# Power.net
KiCad netlist of a schematic drawn in Altium Designer
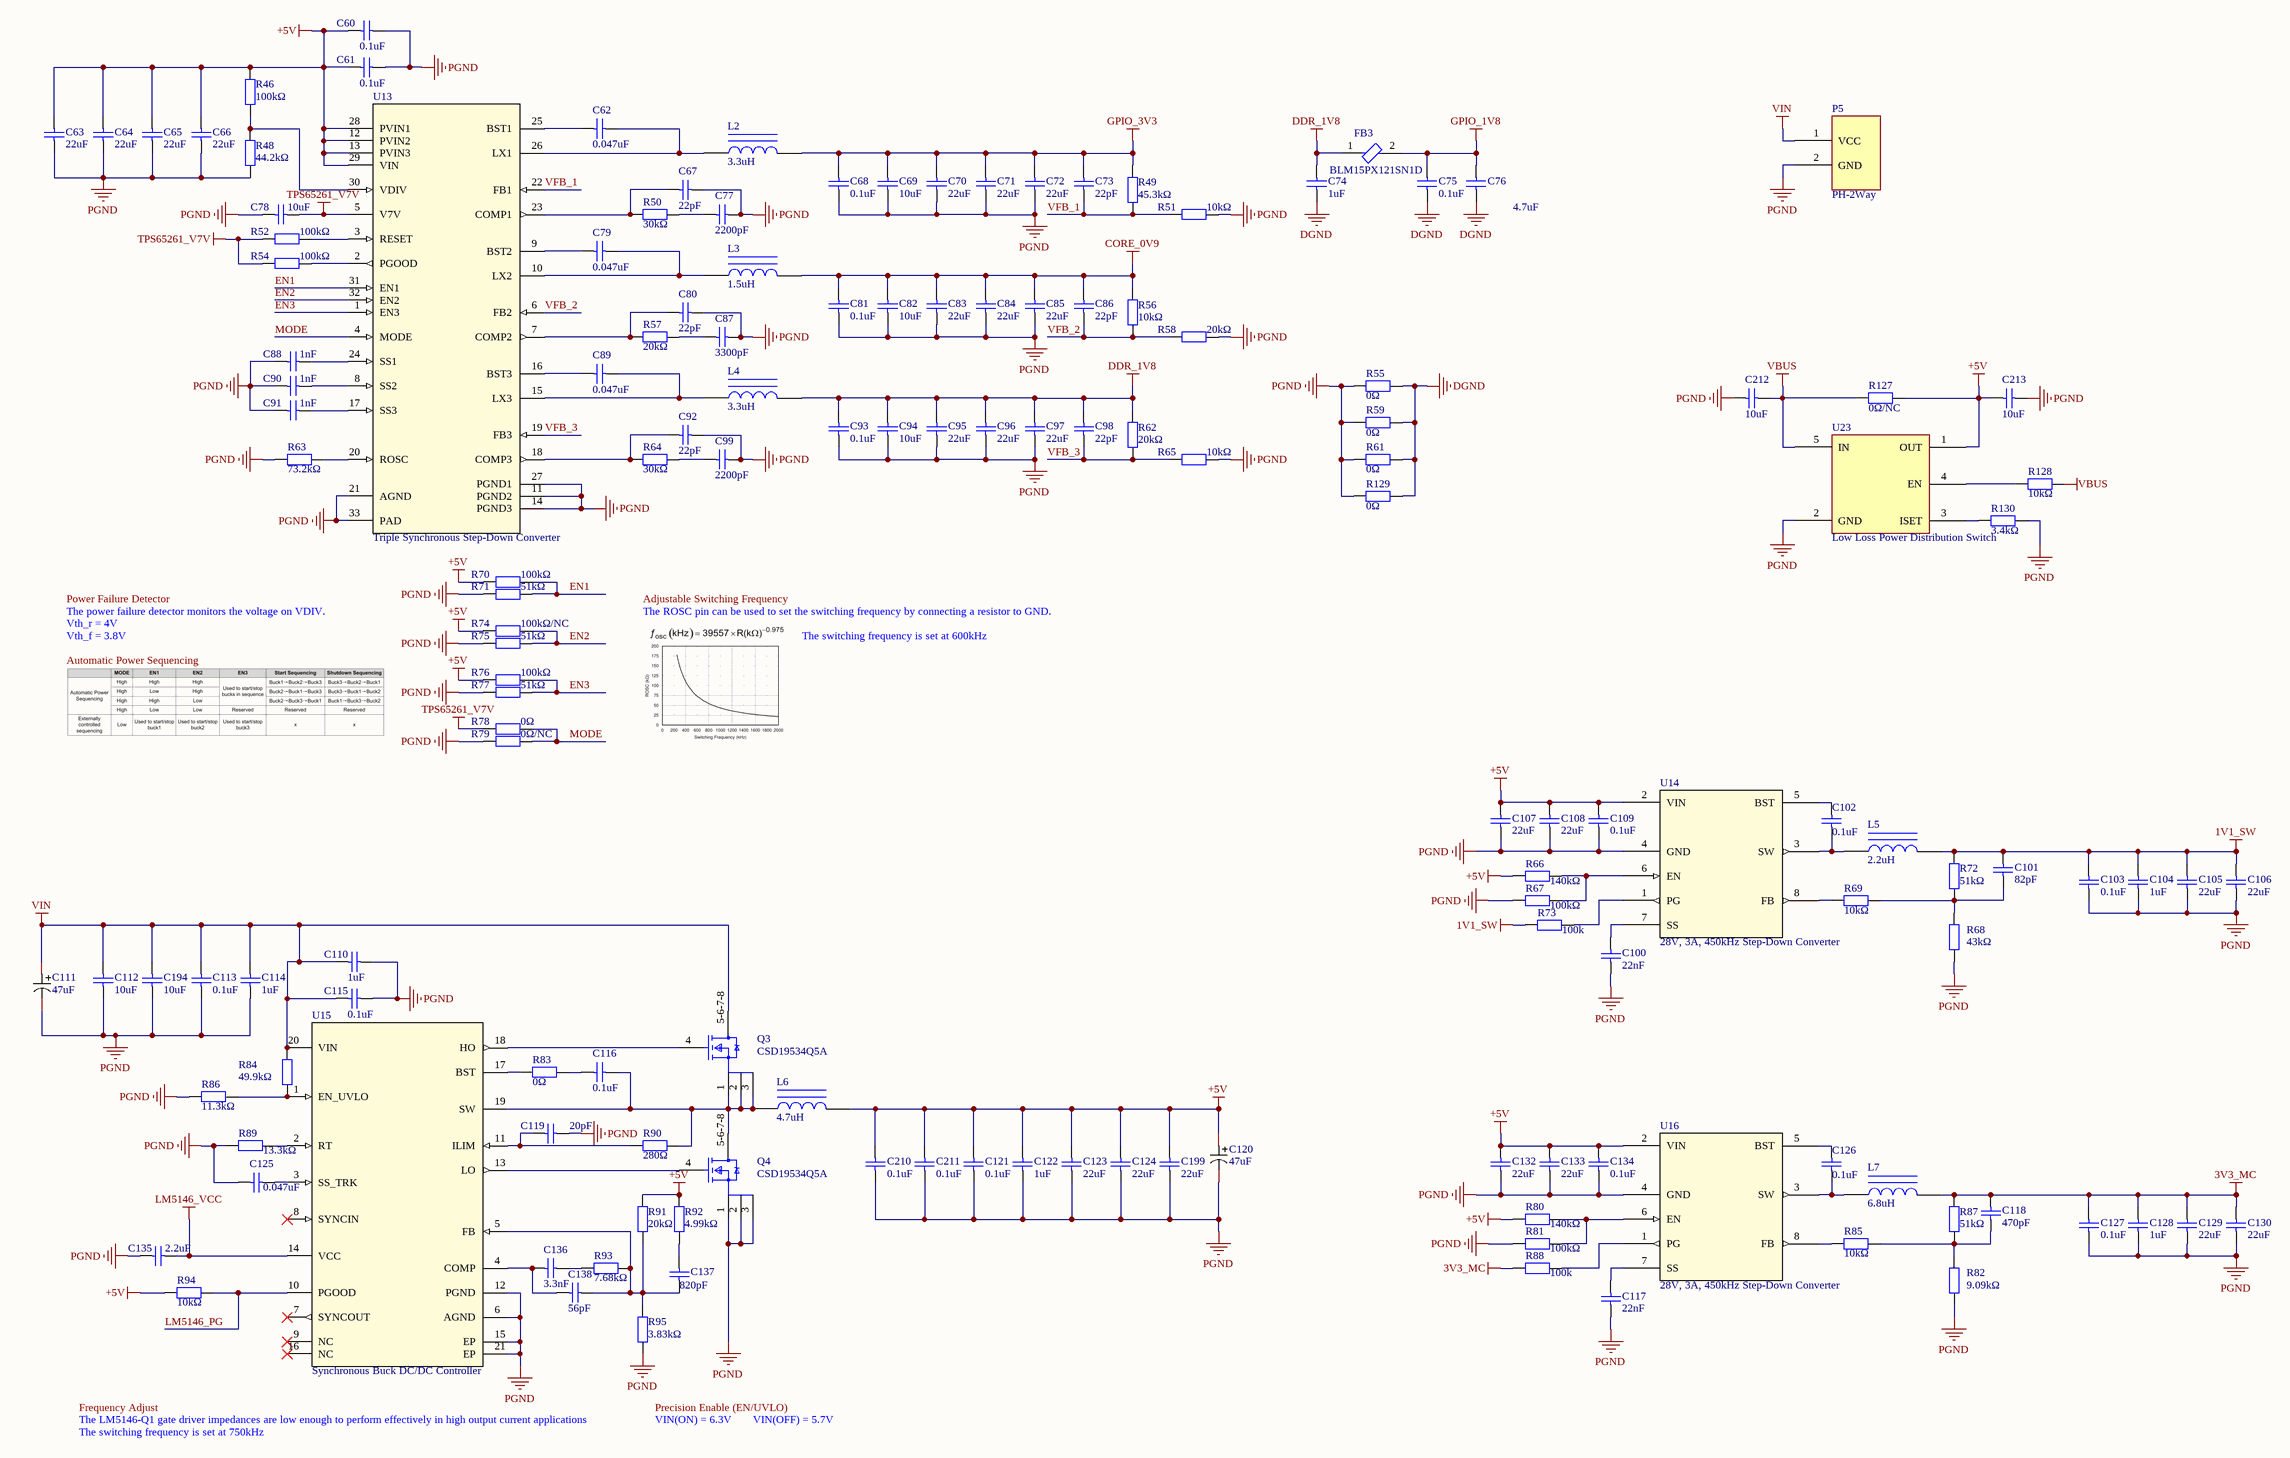
[diagram p0: Power.SchDoc]

(export (version "E")
  (design (tool "Eeschema 10.0.6"))
  (components
    (comp (ref "C60")
      (value "0.1uF")
      (footprint "0603_C")
      (description "贴片电容")
      (libsource (lib "SFerret") (part "SMT_Cap"))
    )
    (comp (ref "C61")
      (value "0.1uF")
      (footprint "0603_C")
      (description "贴片电容")
      (libsource (lib "SFerret") (part "SMT_Cap"))
    )
    (comp (ref "C62")
      (value "0.047uF")
      (footprint "0402_C")
      (description "贴片电容")
      (libsource (lib "SFerret") (part "SMT_Cap"))
    )
    (comp (ref "C63")
      (value "22uF")
      (footprint "1206_C")
      (description "贴片电容")
      (libsource (lib "SFerret") (part "SMT_Cap"))
    )
    (comp (ref "C64")
      (value "22uF")
      (footprint "1206_C")
      (description "贴片电容")
      (libsource (lib "SFerret") (part "SMT_Cap"))
    )
    (comp (ref "C65")
      (value "22uF")
      (footprint "1206_C")
      (description "贴片电容")
      (libsource (lib "SFerret") (part "SMT_Cap"))
    )
    (comp (ref "C66")
      (value "22uF")
      (footprint "1206_C")
      (description "贴片电容")
      (libsource (lib "SFerret") (part "SMT_Cap"))
    )
    (comp (ref "C67")
      (value "22pF")
      (footprint "0402_C")
      (description "贴片电容")
      (libsource (lib "SFerret") (part "SMT_Cap"))
    )
    (comp (ref "C68")
      (value "0.1uF")
      (footprint "0603_C")
      (description "贴片电容")
      (libsource (lib "SFerret") (part "SMT_Cap"))
    )
    (comp (ref "C69")
      (value "10uF")
      (footprint "0603_C")
      (description "贴片电容")
      (libsource (lib "SFerret") (part "SMT_Cap"))
    )
    (comp (ref "C70")
      (value "22uF")
      (footprint "1206_C")
      (description "贴片电容")
      (libsource (lib "SFerret") (part "SMT_Cap"))
    )
    (comp (ref "C71")
      (value "22uF")
      (footprint "1206_C")
      (description "贴片电容")
      (libsource (lib "SFerret") (part "SMT_Cap"))
    )
    (comp (ref "C72")
      (value "22uF")
      (footprint "1206_C")
      (description "贴片电容")
      (libsource (lib "SFerret") (part "SMT_Cap"))
    )
    (comp (ref "C73")
      (value "22pF")
      (footprint "0402_C")
      (description "贴片电容")
      (libsource (lib "SFerret") (part "SMT_Cap"))
    )
    (comp (ref "C74")
      (value "1uF")
      (footprint "0402_C")
      (description "贴片电容")
      (libsource (lib "SFerret") (part "SMT_Cap"))
    )
    (comp (ref "C75")
      (value "0.1uF")
      (footprint "0402_C")
      (description "贴片电容")
      (libsource (lib "SFerret") (part "SMT_Cap"))
    )
    (comp (ref "C76")
      (value "4.7uF")
      (footprint "0402_C")
      (description "贴片电容")
      (libsource (lib "SFerret") (part "SMT_Cap"))
    )
    (comp (ref "C77")
      (value "2200pF")
      (footprint "0402_C")
      (description "贴片电容")
      (libsource (lib "SFerret") (part "SMT_Cap"))
    )
    (comp (ref "C78")
      (value "10uF")
      (footprint "0603_C")
      (description "贴片电容")
      (libsource (lib "SFerret") (part "SMT_Cap"))
    )
    (comp (ref "C79")
      (value "0.047uF")
      (footprint "0402_C")
      (description "贴片电容")
      (libsource (lib "SFerret") (part "SMT_Cap"))
    )
    (comp (ref "C80")
      (value "22pF")
      (footprint "0402_C")
      (description "贴片电容")
      (libsource (lib "SFerret") (part "SMT_Cap"))
    )
    (comp (ref "C81")
      (value "0.1uF")
      (footprint "0603_C")
      (description "贴片电容")
      (libsource (lib "SFerret") (part "SMT_Cap"))
    )
    (comp (ref "C82")
      (value "10uF")
      (footprint "0603_C")
      (description "贴片电容")
      (libsource (lib "SFerret") (part "SMT_Cap"))
    )
    (comp (ref "C83")
      (value "22uF")
      (footprint "1206_C")
      (description "贴片电容")
      (libsource (lib "SFerret") (part "SMT_Cap"))
    )
    (comp (ref "C84")
      (value "22uF")
      (footprint "1206_C")
      (description "贴片电容")
      (libsource (lib "SFerret") (part "SMT_Cap"))
    )
    (comp (ref "C85")
      (value "22uF")
      (footprint "1206_C")
      (description "贴片电容")
      (libsource (lib "SFerret") (part "SMT_Cap"))
    )
    (comp (ref "C86")
      (value "22pF")
      (footprint "0402_C")
      (description "贴片电容")
      (libsource (lib "SFerret") (part "SMT_Cap"))
    )
    (comp (ref "C87")
      (value "3300pF")
      (footprint "0402_C")
      (description "贴片电容")
      (libsource (lib "SFerret") (part "SMT_Cap"))
    )
    (comp (ref "C88")
      (value "1nF")
      (footprint "0402_C")
      (description "贴片电容")
      (libsource (lib "SFerret") (part "SMT_Cap"))
    )
    (comp (ref "C89")
      (value "0.047uF")
      (footprint "0402_C")
      (description "贴片电容")
      (libsource (lib "SFerret") (part "SMT_Cap"))
    )
    (comp (ref "C90")
      (value "1nF")
      (footprint "0402_C")
      (description "贴片电容")
      (libsource (lib "SFerret") (part "SMT_Cap"))
    )
    (comp (ref "C91")
      (value "1nF")
      (footprint "0402_C")
      (description "贴片电容")
      (libsource (lib "SFerret") (part "SMT_Cap"))
    )
    (comp (ref "C92")
      (value "22pF")
      (footprint "0402_C")
      (description "贴片电容")
      (libsource (lib "SFerret") (part "SMT_Cap"))
    )
    (comp (ref "C93")
      (value "0.1uF")
      (footprint "0603_C")
      (description "贴片电容")
      (libsource (lib "SFerret") (part "SMT_Cap"))
    )
    (comp (ref "C94")
      (value "10uF")
      (footprint "0603_C")
      (description "贴片电容")
      (libsource (lib "SFerret") (part "SMT_Cap"))
    )
    (comp (ref "C95")
      (value "22uF")
      (footprint "1206_C")
      (description "贴片电容")
      (libsource (lib "SFerret") (part "SMT_Cap"))
    )
    (comp (ref "C96")
      (value "22uF")
      (footprint "1206_C")
      (description "贴片电容")
      (libsource (lib "SFerret") (part "SMT_Cap"))
    )
    (comp (ref "C97")
      (value "22uF")
      (footprint "1206_C")
      (description "贴片电容")
      (libsource (lib "SFerret") (part "SMT_Cap"))
    )
    (comp (ref "C98")
      (value "22pF")
      (footprint "0402_C")
      (description "贴片电容")
      (libsource (lib "SFerret") (part "SMT_Cap"))
    )
    (comp (ref "C99")
      (value "2200pF")
      (footprint "0402_C")
      (description "贴片电容")
      (libsource (lib "SFerret") (part "SMT_Cap"))
    )
    (comp (ref "C100")
      (value "22nF")
      (footprint "0402_C")
      (description "贴片电容")
      (libsource (lib "SFerret") (part "SMT_Cap"))
    )
    (comp (ref "C101")
      (value "82pF")
      (footprint "0402_C")
      (description "贴片电容")
      (libsource (lib "SFerret") (part "SMT_Cap"))
    )
    (comp (ref "C102")
      (value "0.1uF")
      (footprint "0603_C")
      (description "贴片电容")
      (libsource (lib "SFerret") (part "SMT_Cap"))
    )
    (comp (ref "C103")
      (value "0.1uF")
      (footprint "0603_C")
      (description "贴片电容")
      (libsource (lib "SFerret") (part "SMT_Cap"))
    )
    (comp (ref "C104")
      (value "1uF")
      (footprint "0603_C")
      (description "贴片电容")
      (libsource (lib "SFerret") (part "SMT_Cap"))
    )
    (comp (ref "C105")
      (value "22uF")
      (footprint "1206_C")
      (description "贴片电容")
      (libsource (lib "SFerret") (part "SMT_Cap"))
    )
    (comp (ref "C106")
      (value "22uF")
      (footprint "1206_C")
      (description "贴片电容")
      (libsource (lib "SFerret") (part "SMT_Cap"))
    )
    (comp (ref "C107")
      (value "22uF")
      (footprint "1206_C")
      (description "贴片电容")
      (libsource (lib "SFerret") (part "SMT_Cap"))
    )
    (comp (ref "C108")
      (value "22uF")
      (footprint "1206_C")
      (description "贴片电容")
      (libsource (lib "SFerret") (part "SMT_Cap"))
    )
    (comp (ref "C109")
      (value "0.1uF")
      (footprint "0603_C")
      (description "贴片电容")
      (libsource (lib "SFerret") (part "SMT_Cap"))
    )
    (comp (ref "C110")
      (value "1uF")
      (footprint "0402_C")
      (description "贴片电容")
      (libsource (lib "SFerret") (part "SMT_Cap"))
    )
    (comp (ref "C111")
      (value "47uF")
      (footprint "CM D(6.3*5.4)")
      (description "贴片电容")
      (libsource (lib "SFerret") (part "SMT_Cap_Electrolytic"))
    )
    (comp (ref "C112")
      (value "10uF")
      (footprint "0603_C")
      (description "贴片电容")
      (libsource (lib "SFerret") (part "SMT_Cap"))
    )
    (comp (ref "C113")
      (value "0.1uF")
      (footprint "0603_C")
      (description "贴片电容")
      (libsource (lib "SFerret") (part "SMT_Cap"))
    )
    (comp (ref "C114")
      (value "1uF")
      (footprint "0603_C")
      (description "贴片电容")
      (libsource (lib "SFerret") (part "SMT_Cap"))
    )
    (comp (ref "C115")
      (value "0.1uF")
      (footprint "0402_C")
      (description "贴片电容")
      (libsource (lib "SFerret") (part "SMT_Cap"))
    )
    (comp (ref "C116")
      (value "0.1uF")
      (footprint "0402_C")
      (description "贴片电容")
      (libsource (lib "SFerret") (part "SMT_Cap"))
    )
    (comp (ref "C117")
      (value "22nF")
      (footprint "0402_C")
      (description "贴片电容")
      (libsource (lib "SFerret") (part "SMT_Cap"))
    )
    (comp (ref "C118")
      (value "470pF")
      (footprint "0402_C")
      (description "贴片电容")
      (libsource (lib "SFerret") (part "SMT_Cap"))
    )
    (comp (ref "C119")
      (value "20pF")
      (footprint "0402_C")
      (description "贴片电容")
      (libsource (lib "SFerret") (part "SMT_Cap"))
    )
    (comp (ref "C120")
      (value "47uF")
      (footprint "CM D(6.3*5.4)")
      (description "贴片电容")
      (libsource (lib "SFerret") (part "SMT_Cap_Electrolytic"))
    )
    (comp (ref "C121")
      (value "0.1uF")
      (footprint "0603_C")
      (description "贴片电容")
      (libsource (lib "SFerret") (part "SMT_Cap"))
    )
    (comp (ref "C122")
      (value "1uF")
      (footprint "0603_C")
      (description "贴片电容")
      (libsource (lib "SFerret") (part "SMT_Cap"))
    )
    (comp (ref "C123")
      (value "22uF")
      (footprint "1206_C")
      (description "贴片电容")
      (libsource (lib "SFerret") (part "SMT_Cap"))
    )
    (comp (ref "C124")
      (value "22uF")
      (footprint "1206_C")
      (description "贴片电容")
      (libsource (lib "SFerret") (part "SMT_Cap"))
    )
    (comp (ref "C125")
      (value "0.047uF")
      (footprint "0402_C")
      (description "贴片电容")
      (libsource (lib "SFerret") (part "SMT_Cap"))
    )
    (comp (ref "C126")
      (value "0.1uF")
      (footprint "0603_C")
      (description "贴片电容")
      (libsource (lib "SFerret") (part "SMT_Cap"))
    )
    (comp (ref "C127")
      (value "0.1uF")
      (footprint "0603_C")
      (description "贴片电容")
      (libsource (lib "SFerret") (part "SMT_Cap"))
    )
    (comp (ref "C128")
      (value "1uF")
      (footprint "0603_C")
      (description "贴片电容")
      (libsource (lib "SFerret") (part "SMT_Cap"))
    )
    (comp (ref "C129")
      (value "22uF")
      (footprint "1206_C")
      (description "贴片电容")
      (libsource (lib "SFerret") (part "SMT_Cap"))
    )
    (comp (ref "C130")
      (value "22uF")
      (footprint "1206_C")
      (description "贴片电容")
      (libsource (lib "SFerret") (part "SMT_Cap"))
    )
    (comp (ref "C132")
      (value "22uF")
      (footprint "1206_C")
      (description "贴片电容")
      (libsource (lib "SFerret") (part "SMT_Cap"))
    )
    (comp (ref "C133")
      (value "22uF")
      (footprint "1206_C")
      (description "贴片电容")
      (libsource (lib "SFerret") (part "SMT_Cap"))
    )
    (comp (ref "C134")
      (value "0.1uF")
      (footprint "0603_C")
      (description "贴片电容")
      (libsource (lib "SFerret") (part "SMT_Cap"))
    )
    (comp (ref "C135")
      (value "2.2uF")
      (footprint "0805_C")
      (description "贴片电容")
      (libsource (lib "SFerret") (part "SMT_Cap"))
    )
    (comp (ref "C136")
      (value "3.3nF")
      (footprint "0402_C")
      (description "贴片电容")
      (libsource (lib "SFerret") (part "SMT_Cap"))
    )
    (comp (ref "C137")
      (value "820pF")
      (footprint "0402_C")
      (description "贴片电容")
      (libsource (lib "SFerret") (part "SMT_Cap"))
    )
    (comp (ref "C138")
      (value "56pF")
      (footprint "0402_C")
      (description "贴片电容")
      (libsource (lib "SFerret") (part "SMT_Cap"))
    )
    (comp (ref "C194")
      (value "10uF")
      (footprint "0603_C")
      (description "贴片电容")
      (libsource (lib "SFerret") (part "SMT_Cap"))
    )
    (comp (ref "C199")
      (value "22uF")
      (footprint "1206_C")
      (description "贴片电容")
      (libsource (lib "SFerret") (part "SMT_Cap"))
    )
    (comp (ref "C210")
      (value "0.1uF")
      (footprint "0603_C")
      (description "贴片电容")
      (libsource (lib "SFerret") (part "SMT_Cap"))
    )
    (comp (ref "C211")
      (value "0.1uF")
      (footprint "0603_C")
      (description "贴片电容")
      (libsource (lib "SFerret") (part "SMT_Cap"))
    )
    (comp (ref "C212")
      (value "10uF")
      (footprint "1206_C")
      (description "贴片电容")
      (libsource (lib "SFerret") (part "SMT_Cap"))
    )
    (comp (ref "C213")
      (value "10uF")
      (footprint "1206_C")
      (description "贴片电容")
      (libsource (lib "SFerret") (part "SMT_Cap"))
    )
    (comp (ref "FB3")
      (value "BLM15PX121SN1D")
      (footprint "FP-BLM15-0_05-d0_7-MFG")
      (description "Chip Ferrite Bead, 0402, 120Ω @ 100MHz, 0.055Ω, 25%, 2A")
      (fields (field (name "TOLERANCE") "25%"))
      (libsource (lib "Altium Content Vault") (part "5f30dd21d616792df468990f7003faa"))
    )
    (comp (ref "L2")
      (value "3.3uH")
      (footprint "FTC_3030")
      (description "功率电感")
      (libsource (lib "SFerret") (part "SMT_Iud_Power"))
    )
    (comp (ref "L3")
      (value "1.5uH")
      (footprint "FTC_3030")
      (description "功率电感")
      (libsource (lib "SFerret") (part "SMT_Iud_Power"))
    )
    (comp (ref "L4")
      (value "3.3uH")
      (footprint "FTC_3030")
      (description "功率电感")
      (libsource (lib "SFerret") (part "SMT_Iud_Power"))
    )
    (comp (ref "L5")
      (value "2.2uH")
      (footprint "FTC_3030")
      (description "功率电感")
      (libsource (lib "SFerret") (part "SMT_Iud_Power"))
    )
    (comp (ref "L6")
      (value "4.7uH")
      (footprint "INDM113101X40N")
      (description "功率电感")
      (libsource (lib "SFerret") (part "SMT_Iud_Power"))
    )
    (comp (ref "L7")
      (value "6.8uH")
      (footprint "FTC_3030")
      (description "功率电感")
      (libsource (lib "SFerret") (part "SMT_Iud_Power"))
    )
    (comp (ref "P5") (value "PH-2Way") (footprint "XT30-F") (libsource (lib "SFerret") (part "PH-2Way")))
    (comp (ref "Q3")
      (value "CSD19534Q5A")
      (footprint "FP-DQJ0008A-MFG")
      (description "MOSFET N-CH 100V 50 8SON")
      (fields
        (field (name "OCTOPART") "https://octopart.com/csd19534q5a-texas+instruments-46749514")
        (field (name "MANUFACTURER") "Texas Instruments")
      )
      (libsource (lib "Altium Content Vault") (part "372bcbff2a0099001efc4acc0eb9b45"))
    )
    (comp (ref "Q4")
      (value "CSD19534Q5A")
      (footprint "FP-DQJ0008A-MFG")
      (description "MOSFET N-CH 100V 50 8SON")
      (fields
        (field (name "OCTOPART") "https://octopart.com/csd19534q5a-texas+instruments-46749514")
        (field (name "MANUFACTURER") "Texas Instruments")
      )
      (libsource (lib "Altium Content Vault") (part "372bcbff2a0099001efc4acc0eb9b45"))
    )
    (comp (ref "R46")
      (value "100kΩ")
      (footprint "0402_R")
      (description "贴片电阻")
      (libsource (lib "") (part "SMT_Res_1"))
    )
    (comp (ref "R48")
      (value "44.2kΩ")
      (footprint "0402_R")
      (description "贴片电阻")
      (libsource (lib "") (part "SMT_Res_1"))
    )
    (comp (ref "R49")
      (value "45.3kΩ")
      (footprint "0402_R")
      (description "贴片电阻")
      (libsource (lib "") (part "SMT_Res_1"))
    )
    (comp (ref "R50")
      (value "30kΩ")
      (footprint "0402_R")
      (description "贴片电阻")
      (libsource (lib "SFerret") (part "SMT_Res"))
    )
    (comp (ref "R51")
      (value "10kΩ")
      (footprint "0402_R")
      (description "贴片电阻")
      (libsource (lib "") (part "SMT_Res_2"))
    )
    (comp (ref "R52")
      (value "100kΩ")
      (footprint "0402_R")
      (description "贴片电阻")
      (libsource (lib "SFerret") (part "SMT_Res"))
    )
    (comp (ref "R54")
      (value "100kΩ")
      (footprint "0402_R")
      (description "贴片电阻")
      (libsource (lib "SFerret") (part "SMT_Res"))
    )
    (comp (ref "R55")
      (value "0Ω")
      (footprint "1206_R")
      (description "贴片电阻")
      (libsource (lib "SFerret") (part "SMT_Res"))
    )
    (comp (ref "R56")
      (value "10kΩ")
      (footprint "0402_R")
      (description "贴片电阻")
      (libsource (lib "") (part "SMT_Res_1"))
    )
    (comp (ref "R57")
      (value "20kΩ")
      (footprint "0402_R")
      (description "贴片电阻")
      (libsource (lib "SFerret") (part "SMT_Res"))
    )
    (comp (ref "R58")
      (value "20kΩ")
      (footprint "0402_R")
      (description "贴片电阻")
      (libsource (lib "") (part "SMT_Res_2"))
    )
    (comp (ref "R59")
      (value "0Ω")
      (footprint "1206_R")
      (description "贴片电阻")
      (libsource (lib "SFerret") (part "SMT_Res"))
    )
    (comp (ref "R61")
      (value "0Ω")
      (footprint "1206_R")
      (description "贴片电阻")
      (libsource (lib "SFerret") (part "SMT_Res"))
    )
    (comp (ref "R62")
      (value "20kΩ")
      (footprint "0402_R")
      (description "贴片电阻")
      (libsource (lib "") (part "SMT_Res_1"))
    )
    (comp (ref "R63")
      (value "73.2kΩ")
      (footprint "0402_R")
      (description "贴片电阻")
      (libsource (lib "SFerret") (part "SMT_Res"))
    )
    (comp (ref "R64")
      (value "30kΩ")
      (footprint "0402_R")
      (description "贴片电阻")
      (libsource (lib "SFerret") (part "SMT_Res"))
    )
    (comp (ref "R65")
      (value "10kΩ")
      (footprint "0402_R")
      (description "贴片电阻")
      (libsource (lib "") (part "SMT_Res_2"))
    )
    (comp (ref "R66")
      (value "140kΩ")
      (footprint "0402_R")
      (description "贴片电阻")
      (libsource (lib "") (part "SMT_Res_2"))
    )
    (comp (ref "R67")
      (value "100kΩ")
      (footprint "0402_R")
      (description "贴片电阻")
      (libsource (lib "") (part "SMT_Res_2"))
    )
    (comp (ref "R68")
      (value "43kΩ")
      (footprint "0402_R")
      (description "贴片电阻")
      (libsource (lib "") (part "SMT_Res_1"))
    )
    (comp (ref "R69")
      (value "10kΩ")
      (footprint "0402_R")
      (description "贴片电阻")
      (libsource (lib "") (part "SMT_Res_2"))
    )
    (comp (ref "R70")
      (value "100kΩ")
      (footprint "0402_R")
      (description "贴片电阻")
      (libsource (lib "SFerret") (part "SMT_Res"))
    )
    (comp (ref "R71")
      (value "51kΩ")
      (footprint "0402_R")
      (description "贴片电阻")
      (libsource (lib "") (part "SMT_Res_2"))
    )
    (comp (ref "R72")
      (value "51kΩ")
      (footprint "0402_R")
      (description "贴片电阻")
      (libsource (lib "") (part "SMT_Res_1"))
    )
    (comp (ref "R73")
      (value "100k")
      (footprint "0402_R")
      (description "贴片电阻")
      (libsource (lib "SFerret") (part "SMT_Res"))
    )
    (comp (ref "R74")
      (value "100kΩ/NC")
      (footprint "0402_R")
      (description "贴片电阻")
      (libsource (lib "SFerret") (part "SMT_Res"))
    )
    (comp (ref "R75")
      (value "51kΩ")
      (footprint "0402_R")
      (description "贴片电阻")
      (libsource (lib "") (part "SMT_Res_2"))
    )
    (comp (ref "R76")
      (value "100kΩ")
      (footprint "0402_R")
      (description "贴片电阻")
      (libsource (lib "SFerret") (part "SMT_Res"))
    )
    (comp (ref "R77")
      (value "51kΩ")
      (footprint "0402_R")
      (description "贴片电阻")
      (libsource (lib "") (part "SMT_Res_2"))
    )
    (comp (ref "R78")
      (value "0Ω")
      (footprint "0402_R")
      (description "贴片电阻")
      (libsource (lib "") (part "SMT_Res_2"))
    )
    (comp (ref "R79")
      (value "0Ω/NC")
      (footprint "0402_R")
      (description "贴片电阻")
      (libsource (lib "") (part "SMT_Res_2"))
    )
    (comp (ref "R80")
      (value "140kΩ")
      (footprint "0402_R")
      (description "贴片电阻")
      (libsource (lib "") (part "SMT_Res_2"))
    )
    (comp (ref "R81")
      (value "100kΩ")
      (footprint "0402_R")
      (description "贴片电阻")
      (libsource (lib "") (part "SMT_Res_2"))
    )
    (comp (ref "R82")
      (value "9.09kΩ")
      (footprint "0402_R")
      (description "贴片电阻")
      (libsource (lib "") (part "SMT_Res_1"))
    )
    (comp (ref "R83")
      (value "0Ω")
      (footprint "0402_R")
      (description "贴片电阻")
      (libsource (lib "SFerret") (part "SMT_Res"))
    )
    (comp (ref "R84")
      (value "49.9kΩ")
      (footprint "0402_R")
      (description "贴片电阻")
      (libsource (lib "") (part "SMT_Res_1"))
    )
    (comp (ref "R85")
      (value "10kΩ")
      (footprint "0402_R")
      (description "贴片电阻")
      (libsource (lib "") (part "SMT_Res_2"))
    )
    (comp (ref "R86")
      (value "11.3kΩ")
      (footprint "0402_R")
      (description "贴片电阻")
      (libsource (lib "") (part "SMT_Res_2"))
    )
    (comp (ref "R87")
      (value "51kΩ")
      (footprint "0402_R")
      (description "贴片电阻")
      (libsource (lib "") (part "SMT_Res_1"))
    )
    (comp (ref "R88")
      (value "100k")
      (footprint "0402_R")
      (description "贴片电阻")
      (libsource (lib "SFerret") (part "SMT_Res"))
    )
    (comp (ref "R89")
      (value "13.3kΩ")
      (footprint "0402_R")
      (description "贴片电阻")
      (libsource (lib "") (part "SMT_Res_2"))
    )
    (comp (ref "R90")
      (value "280Ω")
      (footprint "0402_R")
      (description "贴片电阻")
      (libsource (lib "SFerret") (part "SMT_Res"))
    )
    (comp (ref "R91")
      (value "20kΩ")
      (footprint "0402_R")
      (description "贴片电阻")
      (libsource (lib "") (part "SMT_Res_1"))
    )
    (comp (ref "R92")
      (value "4.99kΩ")
      (footprint "0402_R")
      (description "贴片电阻")
      (libsource (lib "") (part "SMT_Res_1"))
    )
    (comp (ref "R93")
      (value "7.68kΩ")
      (footprint "0402_R")
      (description "贴片电阻")
      (libsource (lib "") (part "SMT_Res_2"))
    )
    (comp (ref "R94")
      (value "10kΩ")
      (footprint "0402_R")
      (description "贴片电阻")
      (libsource (lib "") (part "SMT_Res_2"))
    )
    (comp (ref "R95")
      (value "3.83kΩ")
      (footprint "0402_R")
      (description "贴片电阻")
      (libsource (lib "") (part "SMT_Res_1"))
    )
    (comp (ref "R127")
      (value "0Ω/NC")
      (footprint "1206_R")
      (description "贴片电阻")
      (libsource (lib "SFerret") (part "SMT_Res"))
    )
    (comp (ref "R128")
      (value "10kΩ")
      (footprint "0603_R")
      (description "贴片电阻")
      (libsource (lib "SFerret") (part "SMT_Res"))
    )
    (comp (ref "R129")
      (value "0Ω")
      (footprint "1206_R")
      (description "贴片电阻")
      (libsource (lib "SFerret") (part "SMT_Res"))
    )
    (comp (ref "R130")
      (value "3.4kΩ")
      (footprint "0603_R")
      (description "贴片电阻")
      (libsource (lib "") (part "SMT_Res_2"))
    )
    (comp (ref "U13")
      (value "Triple Synchronous Step-Down Converter")
      (footprint "QFN50P500X500X100_HS-33N")
      (fields
        (field (name "PARTNUMBER") "TPS65261RHB")
        (field (name "MANUFACTURER") "Texas Instruments")
        (field (name "MODIFIEDDATE") "Not shown in title block")
        (field (name "APPROVEDBY") "Not shown in title block")
        (field (name "CHECKEDBY") "Not shown in title block")
        (field (name "AUTHOR") "Not shown in title block")
        (field (name "ENGINEER") "Not shown in title block")
        (field (name "SYMBOLCREATOR") "a0411947")
        (field (name "PUBLISHER") "Texas Instruments")
      )
      (libsource (lib "SFerret") (part "TPS65261RHBR"))
    )
    (comp (ref "U14")
      (value "28V, 3A, 450kHz Step-Down Converter")
      (footprint "SOT583_MP2338_MNP")
      (description "High-Efficiency, 28V, 3A, 450kHz,\r\nSynchronous Step-Down Converter\r\nIn SOT583 Package")
      (libsource (lib "SFerret") (part "MP2338GTL-P"))
    )
    (comp (ref "U15")
      (value "Synchronous Buck DC/DC Controller")
      (footprint "RGY0020B")
      (libsource (lib "SFerret") (part "LM5146QRGYRQ1"))
    )
    (comp (ref "U16")
      (value "28V, 3A, 450kHz Step-Down Converter")
      (footprint "SOT583_MP2338_MNP")
      (description "High-Efficiency, 28V, 3A, 450kHz,\r\nSynchronous Step-Down Converter\r\nIn SOT583 Package")
      (libsource (lib "SFerret") (part "MP2338GTL-P"))
    )
    (comp (ref "U23")
      (value "Low Loss Power Distribution Switch")
      (footprint "SOT95P285X130-5N")
      (libsource (lib "SFerret") (part "SY6280"))
    )
  )
  (nets
    (net (code "1") (name "+5V") (class "Default")
      (node (ref "C107") (pin "2") (pinfunction "2_2") (pintype "passive"))
      (node (ref "C108") (pin "2") (pinfunction "2_2") (pintype "passive"))
      (node (ref "C109") (pin "2") (pinfunction "2_2") (pintype "passive"))
      (node (ref "C120") (pin "1") (pinfunction "1_1") (pintype "passive"))
      (node (ref "C121") (pin "2") (pinfunction "2_2") (pintype "passive"))
      (node (ref "C122") (pin "2") (pinfunction "2_2") (pintype "passive"))
      (node (ref "C123") (pin "2") (pinfunction "2_2") (pintype "passive"))
      (node (ref "C124") (pin "2") (pinfunction "2_2") (pintype "passive"))
      (node (ref "C132") (pin "2") (pinfunction "2_2") (pintype "passive"))
      (node (ref "C133") (pin "2") (pinfunction "2_2") (pintype "passive"))
      (node (ref "C134") (pin "2") (pinfunction "2_2") (pintype "passive"))
      (node (ref "C199") (pin "2") (pinfunction "2_2") (pintype "passive"))
      (node (ref "C210") (pin "2") (pinfunction "2_2") (pintype "passive"))
      (node (ref "C211") (pin "2") (pinfunction "2_2") (pintype "passive"))
      (node (ref "C213") (pin "1") (pinfunction "1_1") (pintype "passive"))
      (node (ref "C60") (pin "2") (pinfunction "2_2") (pintype "passive"))
      (node (ref "C61") (pin "2") (pinfunction "2_2") (pintype "passive"))
      (node (ref "C63") (pin "2") (pinfunction "2_2") (pintype "passive"))
      (node (ref "C64") (pin "2") (pinfunction "2_2") (pintype "passive"))
      (node (ref "C65") (pin "2") (pinfunction "2_2") (pintype "passive"))
      (node (ref "C66") (pin "2") (pinfunction "2_2") (pintype "passive"))
      (node (ref "L6") (pin "2") (pinfunction "2_2") (pintype "passive"))
      (node (ref "R127") (pin "2") (pinfunction "2_2") (pintype "passive"))
      (node (ref "R46") (pin "2") (pinfunction "2_2") (pintype "passive"))
      (node (ref "R66") (pin "2") (pinfunction "2_2") (pintype "passive"))
      (node (ref "R70") (pin "1") (pinfunction "1_1") (pintype "passive"))
      (node (ref "R74") (pin "1") (pinfunction "1_1") (pintype "passive"))
      (node (ref "R76") (pin "1") (pinfunction "1_1") (pintype "passive"))
      (node (ref "R80") (pin "2") (pinfunction "2_2") (pintype "passive"))
      (node (ref "R91") (pin "2") (pinfunction "2_2") (pintype "passive"))
      (node (ref "R92") (pin "2") (pinfunction "2_2") (pintype "passive"))
      (node (ref "R94") (pin "2") (pinfunction "2_2") (pintype "passive"))
      (node (ref "U13") (pin "12") (pinfunction "PVIN2_12") (pintype "power_in"))
      (node (ref "U13") (pin "13") (pinfunction "PVIN3_13") (pintype "power_in"))
      (node (ref "U13") (pin "28") (pinfunction "PVIN1_28") (pintype "power_in"))
      (node (ref "U13") (pin "29") (pinfunction "VIN_29") (pintype "power_in"))
      (node (ref "U14") (pin "2") (pinfunction "VIN_2") (pintype "power_in"))
      (node (ref "U16") (pin "2") (pinfunction "VIN_2") (pintype "power_in"))
      (node (ref "U23") (pin "1") (pinfunction "OUT_1") (pintype "passive"))
    )
    (net (code "2") (name "/EN1") (class "Default")
      (node (ref "R70") (pin "2") (pinfunction "2_2") (pintype "passive"))
      (node (ref "R71") (pin "1") (pinfunction "1_1") (pintype "passive"))
      (node (ref "U13") (pin "31") (pinfunction "EN1_31") (pintype "input"))
    )
    (net (code "3") (name "/EN2") (class "Default")
      (node (ref "R74") (pin "2") (pinfunction "2_2") (pintype "passive"))
      (node (ref "R75") (pin "1") (pinfunction "1_1") (pintype "passive"))
      (node (ref "U13") (pin "32") (pinfunction "EN2_32") (pintype "input"))
    )
    (net (code "4") (name "/EN3") (class "Default")
      (node (ref "R76") (pin "2") (pinfunction "2_2") (pintype "passive"))
      (node (ref "R77") (pin "1") (pinfunction "1_1") (pintype "passive"))
      (node (ref "U13") (pin "1") (pinfunction "EN3_1") (pintype "input"))
    )
    (net (code "5") (name "/LM5146_PG") (class "Default")
      (node (ref "R94") (pin "1") (pinfunction "1_1") (pintype "passive"))
      (node (ref "U15") (pin "10") (pinfunction "PGOOD_10") (pintype "open_collector"))
    )
    (net (code "6") (name "/MODE") (class "Default")
      (node (ref "R78") (pin "1") (pinfunction "1_1") (pintype "passive"))
      (node (ref "R79") (pin "1") (pinfunction "1_1") (pintype "passive"))
      (node (ref "U13") (pin "4") (pinfunction "MODE_4") (pintype "input"))
    )
    (net (code "7") (name "/VFB_1") (class "Default")
      (node (ref "C73") (pin "1") (pinfunction "1_1") (pintype "passive"))
      (node (ref "R49") (pin "1") (pinfunction "1_1") (pintype "passive"))
      (node (ref "R51") (pin "2") (pinfunction "2_2") (pintype "passive"))
      (node (ref "U13") (pin "22") (pinfunction "FB1_22") (pintype "input"))
    )
    (net (code "8") (name "/VFB_2") (class "Default")
      (node (ref "C86") (pin "1") (pinfunction "1_1") (pintype "passive"))
      (node (ref "R56") (pin "1") (pinfunction "1_1") (pintype "passive"))
      (node (ref "R58") (pin "2") (pinfunction "2_2") (pintype "passive"))
      (node (ref "U13") (pin "6") (pinfunction "FB2_6") (pintype "input"))
    )
    (net (code "9") (name "/VFB_3") (class "Default")
      (node (ref "C98") (pin "1") (pinfunction "1_1") (pintype "passive"))
      (node (ref "R62") (pin "1") (pinfunction "1_1") (pintype "passive"))
      (node (ref "R65") (pin "2") (pinfunction "2_2") (pintype "passive"))
      (node (ref "U13") (pin "19") (pinfunction "FB3_19") (pintype "input"))
    )
    (net (code "10") (name "1V1_SW") (class "Default")
      (node (ref "C101") (pin "2") (pinfunction "2_2") (pintype "passive"))
      (node (ref "C103") (pin "2") (pinfunction "2_2") (pintype "passive"))
      (node (ref "C104") (pin "2") (pinfunction "2_2") (pintype "passive"))
      (node (ref "C105") (pin "2") (pinfunction "2_2") (pintype "passive"))
      (node (ref "C106") (pin "2") (pinfunction "2_2") (pintype "passive"))
      (node (ref "L5") (pin "2") (pinfunction "2_2") (pintype "passive"))
      (node (ref "R72") (pin "2") (pinfunction "2_2") (pintype "passive"))
      (node (ref "R73") (pin "1") (pinfunction "1_1") (pintype "passive"))
    )
    (net (code "11") (name "3V3_MC") (class "Default")
      (node (ref "C118") (pin "2") (pinfunction "2_2") (pintype "passive"))
      (node (ref "C127") (pin "2") (pinfunction "2_2") (pintype "passive"))
      (node (ref "C128") (pin "2") (pinfunction "2_2") (pintype "passive"))
      (node (ref "C129") (pin "2") (pinfunction "2_2") (pintype "passive"))
      (node (ref "C130") (pin "2") (pinfunction "2_2") (pintype "passive"))
      (node (ref "L7") (pin "2") (pinfunction "2_2") (pintype "passive"))
      (node (ref "R87") (pin "2") (pinfunction "2_2") (pintype "passive"))
      (node (ref "R88") (pin "1") (pinfunction "1_1") (pintype "passive"))
    )
    (net (code "12") (name "CORE_0V9") (class "Default")
      (node (ref "C81") (pin "2") (pinfunction "2_2") (pintype "passive"))
      (node (ref "C82") (pin "2") (pinfunction "2_2") (pintype "passive"))
      (node (ref "C83") (pin "2") (pinfunction "2_2") (pintype "passive"))
      (node (ref "C84") (pin "2") (pinfunction "2_2") (pintype "passive"))
      (node (ref "C85") (pin "2") (pinfunction "2_2") (pintype "passive"))
      (node (ref "C86") (pin "2") (pinfunction "2_2") (pintype "passive"))
      (node (ref "L3") (pin "2") (pinfunction "2_2") (pintype "passive"))
      (node (ref "R56") (pin "2") (pinfunction "2_2") (pintype "passive"))
    )
    (net (code "13") (name "DDR_1V8") (class "Default")
      (node (ref "C74") (pin "2") (pinfunction "2_2") (pintype "passive"))
      (node (ref "C93") (pin "2") (pinfunction "2_2") (pintype "passive"))
      (node (ref "C94") (pin "2") (pinfunction "2_2") (pintype "passive"))
      (node (ref "C95") (pin "2") (pinfunction "2_2") (pintype "passive"))
      (node (ref "C96") (pin "2") (pinfunction "2_2") (pintype "passive"))
      (node (ref "C97") (pin "2") (pinfunction "2_2") (pintype "passive"))
      (node (ref "C98") (pin "2") (pinfunction "2_2") (pintype "passive"))
      (node (ref "FB3") (pin "1") (pinfunction "1_1") (pintype "passive"))
      (node (ref "L4") (pin "2") (pinfunction "2_2") (pintype "passive"))
      (node (ref "R62") (pin "2") (pinfunction "2_2") (pintype "passive"))
    )
    (net (code "14") (name "DGND") (class "Default")
      (node (ref "C74") (pin "1") (pinfunction "1_1") (pintype "passive"))
      (node (ref "C75") (pin "1") (pinfunction "1_1") (pintype "passive"))
      (node (ref "C76") (pin "1") (pinfunction "1_1") (pintype "passive"))
      (node (ref "R129") (pin "2") (pinfunction "2_2") (pintype "passive"))
      (node (ref "R55") (pin "2") (pinfunction "2_2") (pintype "passive"))
      (node (ref "R59") (pin "2") (pinfunction "2_2") (pintype "passive"))
      (node (ref "R61") (pin "2") (pinfunction "2_2") (pintype "passive"))
    )
    (net (code "15") (name "GPIO_1V8") (class "Default")
      (node (ref "C75") (pin "2") (pinfunction "2_2") (pintype "passive"))
      (node (ref "C76") (pin "2") (pinfunction "2_2") (pintype "passive"))
      (node (ref "FB3") (pin "2") (pinfunction "2_2") (pintype "passive"))
    )
    (net (code "16") (name "GPIO_3V3") (class "Default")
      (node (ref "C68") (pin "2") (pinfunction "2_2") (pintype "passive"))
      (node (ref "C69") (pin "2") (pinfunction "2_2") (pintype "passive"))
      (node (ref "C70") (pin "2") (pinfunction "2_2") (pintype "passive"))
      (node (ref "C71") (pin "2") (pinfunction "2_2") (pintype "passive"))
      (node (ref "C72") (pin "2") (pinfunction "2_2") (pintype "passive"))
      (node (ref "C73") (pin "2") (pinfunction "2_2") (pintype "passive"))
      (node (ref "L2") (pin "2") (pinfunction "2_2") (pintype "passive"))
      (node (ref "R49") (pin "2") (pinfunction "2_2") (pintype "passive"))
    )
    (net (code "17") (name "LM5146_VCC") (class "Default")
      (node (ref "C135") (pin "1") (pinfunction "1_1") (pintype "passive"))
      (node (ref "U15") (pin "14") (pinfunction "VCC_14") (pintype "power_in"))
    )
    (net (code "18") (name "Net-(C77-Pad1)") (class "Default")
      (node (ref "C77") (pin "1") (pinfunction "1_1") (pintype "passive"))
      (node (ref "R50") (pin "2") (pinfunction "2_2") (pintype "passive"))
    )
    (net (code "19") (name "Net-(C87-Pad1)") (class "Default")
      (node (ref "C87") (pin "1") (pinfunction "1_1") (pintype "passive"))
      (node (ref "R57") (pin "2") (pinfunction "2_2") (pintype "passive"))
    )
    (net (code "20") (name "Net-(C99-Pad1)") (class "Default")
      (node (ref "C99") (pin "1") (pinfunction "1_1") (pintype "passive"))
      (node (ref "R64") (pin "2") (pinfunction "2_2") (pintype "passive"))
    )
    (net (code "21") (name "Net-(C101-Pad1)") (class "Default")
      (node (ref "C101") (pin "1") (pinfunction "1_1") (pintype "passive"))
      (node (ref "R68") (pin "2") (pinfunction "2_2") (pintype "passive"))
      (node (ref "R69") (pin "1") (pinfunction "1_1") (pintype "passive"))
      (node (ref "R72") (pin "1") (pinfunction "1_1") (pintype "passive"))
    )
    (net (code "22") (name "Net-(C116-Pad1)") (class "Default")
      (node (ref "C116") (pin "1") (pinfunction "1_1") (pintype "passive"))
      (node (ref "R83") (pin "2") (pinfunction "2_2") (pintype "passive"))
    )
    (net (code "23") (name "Net-(C118-Pad1)") (class "Default")
      (node (ref "C118") (pin "1") (pinfunction "1_1") (pintype "passive"))
      (node (ref "R82") (pin "2") (pinfunction "2_2") (pintype "passive"))
      (node (ref "R85") (pin "1") (pinfunction "1_1") (pintype "passive"))
      (node (ref "R87") (pin "1") (pinfunction "1_1") (pintype "passive"))
    )
    (net (code "24") (name "Net-(C136-Pad1)") (class "Default")
      (node (ref "C136") (pin "1") (pinfunction "1_1") (pintype "passive"))
      (node (ref "R93") (pin "2") (pinfunction "2_2") (pintype "passive"))
    )
    (net (code "25") (name "Net-(C137-Pad2)") (class "Default")
      (node (ref "C137") (pin "2") (pinfunction "2_2") (pintype "passive"))
      (node (ref "R92") (pin "1") (pinfunction "1_1") (pintype "passive"))
    )
    (net (code "26") (name "Net-(Q3-G)") (class "Default")
      (node (ref "Q3") (pin "4") (pinfunction "G_4") (pintype "passive"))
      (node (ref "U15") (pin "18") (pinfunction "HO_18") (pintype "output"))
    )
    (net (code "27") (name "Net-(Q4-D)") (class "Default")
      (node (ref "C116") (pin "2") (pinfunction "2_2") (pintype "passive"))
      (node (ref "L6") (pin "1") (pinfunction "1_1") (pintype "passive"))
      (node (ref "Q3") (pin "1") (pinfunction "S_1") (pintype "passive"))
      (node (ref "Q3") (pin "2") (pinfunction "S_2") (pintype "passive"))
      (node (ref "Q3") (pin "3") (pinfunction "S_3") (pintype "passive"))
      (node (ref "Q4") (pin "5-6-7-8") (pinfunction "D_5-6-7-8") (pintype "passive"))
      (node (ref "R90") (pin "2") (pinfunction "2_2") (pintype "passive"))
      (node (ref "U15") (pin "19") (pinfunction "SW_19") (pintype "power_in"))
    )
    (net (code "28") (name "Net-(Q4-G)") (class "Default")
      (node (ref "Q4") (pin "4") (pinfunction "G_4") (pintype "passive"))
      (node (ref "U15") (pin "13") (pinfunction "LO_13") (pintype "output"))
    )
    (net (code "29") (name "Net-(U13-BST1)") (class "Default")
      (node (ref "C62") (pin "1") (pinfunction "1_1") (pintype "passive"))
      (node (ref "U13") (pin "25") (pinfunction "BST1_25") (pintype "power_in"))
    )
    (net (code "30") (name "Net-(U13-BST2)") (class "Default")
      (node (ref "C79") (pin "1") (pinfunction "1_1") (pintype "passive"))
      (node (ref "U13") (pin "9") (pinfunction "BST2_9") (pintype "power_in"))
    )
    (net (code "31") (name "Net-(U13-BST3)") (class "Default")
      (node (ref "C89") (pin "1") (pinfunction "1_1") (pintype "passive"))
      (node (ref "U13") (pin "16") (pinfunction "BST3_16") (pintype "power_in"))
    )
    (net (code "32") (name "Net-(U13-COMP1)") (class "Default")
      (node (ref "C67") (pin "1") (pinfunction "1_1") (pintype "passive"))
      (node (ref "R50") (pin "1") (pinfunction "1_1") (pintype "passive"))
      (node (ref "U13") (pin "23") (pinfunction "COMP1_23") (pintype "output"))
    )
    (net (code "33") (name "Net-(U13-COMP2)") (class "Default")
      (node (ref "C80") (pin "1") (pinfunction "1_1") (pintype "passive"))
      (node (ref "R57") (pin "1") (pinfunction "1_1") (pintype "passive"))
      (node (ref "U13") (pin "7") (pinfunction "COMP2_7") (pintype "output"))
    )
    (net (code "34") (name "Net-(U13-COMP3)") (class "Default")
      (node (ref "C92") (pin "1") (pinfunction "1_1") (pintype "passive"))
      (node (ref "R64") (pin "1") (pinfunction "1_1") (pintype "passive"))
      (node (ref "U13") (pin "18") (pinfunction "COMP3_18") (pintype "output"))
    )
    (net (code "35") (name "Net-(U13-LX1)") (class "Default")
      (node (ref "C62") (pin "2") (pinfunction "2_2") (pintype "passive"))
      (node (ref "L2") (pin "1") (pinfunction "1_1") (pintype "passive"))
      (node (ref "U13") (pin "26") (pinfunction "LX1_26") (pintype "power_in"))
    )
    (net (code "36") (name "Net-(U13-LX2)") (class "Default")
      (node (ref "C79") (pin "2") (pinfunction "2_2") (pintype "passive"))
      (node (ref "L3") (pin "1") (pinfunction "1_1") (pintype "passive"))
      (node (ref "U13") (pin "10") (pinfunction "LX2_10") (pintype "power_in"))
    )
    (net (code "37") (name "Net-(U13-LX3)") (class "Default")
      (node (ref "C89") (pin "2") (pinfunction "2_2") (pintype "passive"))
      (node (ref "L4") (pin "1") (pinfunction "1_1") (pintype "passive"))
      (node (ref "U13") (pin "15") (pinfunction "LX3_15") (pintype "power_in"))
    )
    (net (code "38") (name "Net-(U13-PGOOD)") (class "Default")
      (node (ref "R54") (pin "2") (pinfunction "2_2") (pintype "passive"))
      (node (ref "U13") (pin "2") (pinfunction "PGOOD_2") (pintype "output"))
    )
    (net (code "39") (name "Net-(U13-RESET)") (class "Default")
      (node (ref "R52") (pin "2") (pinfunction "2_2") (pintype "passive"))
      (node (ref "U13") (pin "3") (pinfunction "RESET_3") (pintype "input"))
    )
    (net (code "40") (name "Net-(U13-ROSC)") (class "Default")
      (node (ref "R63") (pin "2") (pinfunction "2_2") (pintype "passive"))
      (node (ref "U13") (pin "20") (pinfunction "ROSC_20") (pintype "input"))
    )
    (net (code "41") (name "Net-(U13-SS1)") (class "Default")
      (node (ref "C88") (pin "2") (pinfunction "2_2") (pintype "passive"))
      (node (ref "U13") (pin "24") (pinfunction "SS1_24") (pintype "input"))
    )
    (net (code "42") (name "Net-(U13-SS2)") (class "Default")
      (node (ref "C90") (pin "2") (pinfunction "2_2") (pintype "passive"))
      (node (ref "U13") (pin "8") (pinfunction "SS2_8") (pintype "input"))
    )
    (net (code "43") (name "Net-(U13-SS3)") (class "Default")
      (node (ref "C91") (pin "2") (pinfunction "2_2") (pintype "passive"))
      (node (ref "U13") (pin "17") (pinfunction "SS3_17") (pintype "input"))
    )
    (net (code "44") (name "Net-(U13-VDIV)") (class "Default")
      (node (ref "R46") (pin "1") (pinfunction "1_1") (pintype "passive"))
      (node (ref "R48") (pin "2") (pinfunction "2_2") (pintype "passive"))
      (node (ref "U13") (pin "30") (pinfunction "VDIV_30") (pintype "input"))
    )
    (net (code "45") (name "Net-(U14-BST)") (class "Default")
      (node (ref "C102") (pin "2") (pinfunction "2_2") (pintype "passive"))
      (node (ref "U14") (pin "5") (pinfunction "BST_5") (pintype "power_in"))
    )
    (net (code "46") (name "Net-(U14-EN)") (class "Default")
      (node (ref "R66") (pin "1") (pinfunction "1_1") (pintype "passive"))
      (node (ref "R67") (pin "1") (pinfunction "1_1") (pintype "passive"))
      (node (ref "U14") (pin "6") (pinfunction "EN_6") (pintype "input"))
    )
    (net (code "47") (name "Net-(U14-FB)") (class "Default")
      (node (ref "R69") (pin "2") (pinfunction "2_2") (pintype "passive"))
      (node (ref "U14") (pin "8") (pinfunction "FB_8") (pintype "output"))
    )
    (net (code "48") (name "Net-(U14-PG)") (class "Default")
      (node (ref "R73") (pin "2") (pinfunction "2_2") (pintype "passive"))
      (node (ref "U14") (pin "1") (pinfunction "PG_1") (pintype "output"))
    )
    (net (code "49") (name "Net-(U14-SS)") (class "Default")
      (node (ref "C100") (pin "2") (pinfunction "2_2") (pintype "passive"))
      (node (ref "U14") (pin "7") (pinfunction "SS_7") (pintype "passive"))
    )
    (net (code "50") (name "Net-(U14-SW)") (class "Default")
      (node (ref "C102") (pin "1") (pinfunction "1_1") (pintype "passive"))
      (node (ref "L5") (pin "1") (pinfunction "1_1") (pintype "passive"))
      (node (ref "U14") (pin "3") (pinfunction "SW_3") (pintype "output"))
    )
    (net (code "51") (name "Net-(U15-BST)") (class "Default")
      (node (ref "R83") (pin "1") (pinfunction "1_1") (pintype "passive"))
      (node (ref "U15") (pin "17") (pinfunction "BST_17") (pintype "passive"))
    )
    (net (code "52") (name "Net-(U15-COMP)") (class "Default")
      (node (ref "C136") (pin "2") (pinfunction "2_2") (pintype "passive"))
      (node (ref "C138") (pin "2") (pinfunction "2_2") (pintype "passive"))
      (node (ref "U15") (pin "4") (pinfunction "COMP_4") (pintype "passive"))
    )
    (net (code "53") (name "Net-(U15-EN_UVLO)") (class "Default")
      (node (ref "R84") (pin "1") (pinfunction "1_1") (pintype "passive"))
      (node (ref "R86") (pin "1") (pinfunction "1_1") (pintype "passive"))
      (node (ref "U15") (pin "1") (pinfunction "EN_UVLO_1") (pintype "input"))
    )
    (net (code "54") (name "Net-(U15-FB)") (class "Default")
      (node (ref "C137") (pin "1") (pinfunction "1_1") (pintype "passive"))
      (node (ref "C138") (pin "1") (pinfunction "1_1") (pintype "passive"))
      (node (ref "R91") (pin "1") (pinfunction "1_1") (pintype "passive"))
      (node (ref "R93") (pin "1") (pinfunction "1_1") (pintype "passive"))
      (node (ref "R95") (pin "2") (pinfunction "2_2") (pintype "passive"))
      (node (ref "U15") (pin "5") (pinfunction "FB_5") (pintype "input"))
    )
    (net (code "55") (name "Net-(U15-ILIM)") (class "Default")
      (node (ref "C119") (pin "1") (pinfunction "1_1") (pintype "passive"))
      (node (ref "R90") (pin "1") (pinfunction "1_1") (pintype "passive"))
      (node (ref "U15") (pin "11") (pinfunction "ILIM_11") (pintype "input"))
    )
    (net (code "56") (name "Net-(U15-RT)") (class "Default")
      (node (ref "R89") (pin "1") (pinfunction "1_1") (pintype "passive"))
      (node (ref "U15") (pin "2") (pinfunction "RT_2") (pintype "input"))
    )
    (net (code "57") (name "Net-(U15-SS_TRK)") (class "Default")
      (node (ref "C125") (pin "1") (pinfunction "1_1") (pintype "passive"))
      (node (ref "U15") (pin "3") (pinfunction "SS_TRK_3") (pintype "input"))
    )
    (net (code "58") (name "Net-(U16-BST)") (class "Default")
      (node (ref "C126") (pin "2") (pinfunction "2_2") (pintype "passive"))
      (node (ref "U16") (pin "5") (pinfunction "BST_5") (pintype "power_in"))
    )
    (net (code "59") (name "Net-(U16-EN)") (class "Default")
      (node (ref "R80") (pin "1") (pinfunction "1_1") (pintype "passive"))
      (node (ref "R81") (pin "1") (pinfunction "1_1") (pintype "passive"))
      (node (ref "U16") (pin "6") (pinfunction "EN_6") (pintype "input"))
    )
    (net (code "60") (name "Net-(U16-FB)") (class "Default")
      (node (ref "R85") (pin "2") (pinfunction "2_2") (pintype "passive"))
      (node (ref "U16") (pin "8") (pinfunction "FB_8") (pintype "output"))
    )
    (net (code "61") (name "Net-(U16-PG)") (class "Default")
      (node (ref "R88") (pin "2") (pinfunction "2_2") (pintype "passive"))
      (node (ref "U16") (pin "1") (pinfunction "PG_1") (pintype "output"))
    )
    (net (code "62") (name "Net-(U16-SS)") (class "Default")
      (node (ref "C117") (pin "1") (pinfunction "1_1") (pintype "passive"))
      (node (ref "U16") (pin "7") (pinfunction "SS_7") (pintype "passive"))
    )
    (net (code "63") (name "Net-(U16-SW)") (class "Default")
      (node (ref "C126") (pin "1") (pinfunction "1_1") (pintype "passive"))
      (node (ref "L7") (pin "1") (pinfunction "1_1") (pintype "passive"))
      (node (ref "U16") (pin "3") (pinfunction "SW_3") (pintype "output"))
    )
    (net (code "64") (name "Net-(U23-EN)") (class "Default")
      (node (ref "R128") (pin "1") (pinfunction "1_1") (pintype "passive"))
      (node (ref "U23") (pin "4") (pinfunction "EN_4") (pintype "passive"))
    )
    (net (code "65") (name "Net-(U23-ISET)") (class "Default")
      (node (ref "R130") (pin "2") (pinfunction "2_2") (pintype "passive"))
      (node (ref "U23") (pin "3") (pinfunction "ISET_3") (pintype "passive"))
    )
    (net (code "66") (name "PGND") (class "Default")
      (node (ref "C100") (pin "1") (pinfunction "1_1") (pintype "passive"))
      (node (ref "C103") (pin "1") (pinfunction "1_1") (pintype "passive"))
      (node (ref "C104") (pin "1") (pinfunction "1_1") (pintype "passive"))
      (node (ref "C105") (pin "1") (pinfunction "1_1") (pintype "passive"))
      (node (ref "C106") (pin "1") (pinfunction "1_1") (pintype "passive"))
      (node (ref "C107") (pin "1") (pinfunction "1_1") (pintype "passive"))
      (node (ref "C108") (pin "1") (pinfunction "1_1") (pintype "passive"))
      (node (ref "C109") (pin "1") (pinfunction "1_1") (pintype "passive"))
      (node (ref "C110") (pin "1") (pinfunction "1_1") (pintype "passive"))
      (node (ref "C111") (pin "2") (pinfunction "2_2") (pintype "passive"))
      (node (ref "C112") (pin "2") (pinfunction "2_2") (pintype "passive"))
      (node (ref "C113") (pin "2") (pinfunction "2_2") (pintype "passive"))
      (node (ref "C114") (pin "2") (pinfunction "2_2") (pintype "passive"))
      (node (ref "C115") (pin "1") (pinfunction "1_1") (pintype "passive"))
      (node (ref "C117") (pin "2") (pinfunction "2_2") (pintype "passive"))
      (node (ref "C119") (pin "2") (pinfunction "2_2") (pintype "passive"))
      (node (ref "C120") (pin "2") (pinfunction "2_2") (pintype "passive"))
      (node (ref "C121") (pin "1") (pinfunction "1_1") (pintype "passive"))
      (node (ref "C122") (pin "1") (pinfunction "1_1") (pintype "passive"))
      (node (ref "C123") (pin "1") (pinfunction "1_1") (pintype "passive"))
      (node (ref "C124") (pin "1") (pinfunction "1_1") (pintype "passive"))
      (node (ref "C125") (pin "2") (pinfunction "2_2") (pintype "passive"))
      (node (ref "C127") (pin "1") (pinfunction "1_1") (pintype "passive"))
      (node (ref "C128") (pin "1") (pinfunction "1_1") (pintype "passive"))
      (node (ref "C129") (pin "1") (pinfunction "1_1") (pintype "passive"))
      (node (ref "C130") (pin "1") (pinfunction "1_1") (pintype "passive"))
      (node (ref "C132") (pin "1") (pinfunction "1_1") (pintype "passive"))
      (node (ref "C133") (pin "1") (pinfunction "1_1") (pintype "passive"))
      (node (ref "C134") (pin "1") (pinfunction "1_1") (pintype "passive"))
      (node (ref "C135") (pin "2") (pinfunction "2_2") (pintype "passive"))
      (node (ref "C194") (pin "2") (pinfunction "2_2") (pintype "passive"))
      (node (ref "C199") (pin "1") (pinfunction "1_1") (pintype "passive"))
      (node (ref "C210") (pin "1") (pinfunction "1_1") (pintype "passive"))
      (node (ref "C211") (pin "1") (pinfunction "1_1") (pintype "passive"))
      (node (ref "C212") (pin "2") (pinfunction "2_2") (pintype "passive"))
      (node (ref "C213") (pin "2") (pinfunction "2_2") (pintype "passive"))
      (node (ref "C60") (pin "1") (pinfunction "1_1") (pintype "passive"))
      (node (ref "C61") (pin "1") (pinfunction "1_1") (pintype "passive"))
      (node (ref "C63") (pin "1") (pinfunction "1_1") (pintype "passive"))
      (node (ref "C64") (pin "1") (pinfunction "1_1") (pintype "passive"))
      (node (ref "C65") (pin "1") (pinfunction "1_1") (pintype "passive"))
      (node (ref "C66") (pin "1") (pinfunction "1_1") (pintype "passive"))
      (node (ref "C67") (pin "2") (pinfunction "2_2") (pintype "passive"))
      (node (ref "C68") (pin "1") (pinfunction "1_1") (pintype "passive"))
      (node (ref "C69") (pin "1") (pinfunction "1_1") (pintype "passive"))
      (node (ref "C70") (pin "1") (pinfunction "1_1") (pintype "passive"))
      (node (ref "C71") (pin "1") (pinfunction "1_1") (pintype "passive"))
      (node (ref "C72") (pin "1") (pinfunction "1_1") (pintype "passive"))
      (node (ref "C77") (pin "2") (pinfunction "2_2") (pintype "passive"))
      (node (ref "C78") (pin "1") (pinfunction "1_1") (pintype "passive"))
      (node (ref "C80") (pin "2") (pinfunction "2_2") (pintype "passive"))
      (node (ref "C81") (pin "1") (pinfunction "1_1") (pintype "passive"))
      (node (ref "C82") (pin "1") (pinfunction "1_1") (pintype "passive"))
      (node (ref "C83") (pin "1") (pinfunction "1_1") (pintype "passive"))
      (node (ref "C84") (pin "1") (pinfunction "1_1") (pintype "passive"))
      (node (ref "C85") (pin "1") (pinfunction "1_1") (pintype "passive"))
      (node (ref "C87") (pin "2") (pinfunction "2_2") (pintype "passive"))
      (node (ref "C88") (pin "1") (pinfunction "1_1") (pintype "passive"))
      (node (ref "C90") (pin "1") (pinfunction "1_1") (pintype "passive"))
      (node (ref "C91") (pin "1") (pinfunction "1_1") (pintype "passive"))
      (node (ref "C92") (pin "2") (pinfunction "2_2") (pintype "passive"))
      (node (ref "C93") (pin "1") (pinfunction "1_1") (pintype "passive"))
      (node (ref "C94") (pin "1") (pinfunction "1_1") (pintype "passive"))
      (node (ref "C95") (pin "1") (pinfunction "1_1") (pintype "passive"))
      (node (ref "C96") (pin "1") (pinfunction "1_1") (pintype "passive"))
      (node (ref "C97") (pin "1") (pinfunction "1_1") (pintype "passive"))
      (node (ref "C99") (pin "2") (pinfunction "2_2") (pintype "passive"))
      (node (ref "P5") (pin "2") (pinfunction "GND_2") (pintype "passive"))
      (node (ref "Q4") (pin "1") (pinfunction "S_1") (pintype "passive"))
      (node (ref "Q4") (pin "2") (pinfunction "S_2") (pintype "passive"))
      (node (ref "Q4") (pin "3") (pinfunction "S_3") (pintype "passive"))
      (node (ref "R129") (pin "1") (pinfunction "1_1") (pintype "passive"))
      (node (ref "R130") (pin "1") (pinfunction "1_1") (pintype "passive"))
      (node (ref "R48") (pin "1") (pinfunction "1_1") (pintype "passive"))
      (node (ref "R51") (pin "1") (pinfunction "1_1") (pintype "passive"))
      (node (ref "R55") (pin "1") (pinfunction "1_1") (pintype "passive"))
      (node (ref "R58") (pin "1") (pinfunction "1_1") (pintype "passive"))
      (node (ref "R59") (pin "1") (pinfunction "1_1") (pintype "passive"))
      (node (ref "R61") (pin "1") (pinfunction "1_1") (pintype "passive"))
      (node (ref "R63") (pin "1") (pinfunction "1_1") (pintype "passive"))
      (node (ref "R65") (pin "1") (pinfunction "1_1") (pintype "passive"))
      (node (ref "R67") (pin "2") (pinfunction "2_2") (pintype "passive"))
      (node (ref "R68") (pin "1") (pinfunction "1_1") (pintype "passive"))
      (node (ref "R71") (pin "2") (pinfunction "2_2") (pintype "passive"))
      (node (ref "R75") (pin "2") (pinfunction "2_2") (pintype "passive"))
      (node (ref "R77") (pin "2") (pinfunction "2_2") (pintype "passive"))
      (node (ref "R79") (pin "2") (pinfunction "2_2") (pintype "passive"))
      (node (ref "R81") (pin "2") (pinfunction "2_2") (pintype "passive"))
      (node (ref "R82") (pin "1") (pinfunction "1_1") (pintype "passive"))
      (node (ref "R86") (pin "2") (pinfunction "2_2") (pintype "passive"))
      (node (ref "R89") (pin "2") (pinfunction "2_2") (pintype "passive"))
      (node (ref "R95") (pin "1") (pinfunction "1_1") (pintype "passive"))
      (node (ref "U13") (pin "11") (pinfunction "PGND2_11") (pintype "power_in"))
      (node (ref "U13") (pin "14") (pinfunction "PGND3_14") (pintype "power_in"))
      (node (ref "U13") (pin "21") (pinfunction "AGND_21") (pintype "power_in"))
      (node (ref "U13") (pin "27") (pinfunction "PGND1_27") (pintype "power_in"))
      (node (ref "U13") (pin "33") (pinfunction "PAD_33") (pintype "passive"))
      (node (ref "U14") (pin "4") (pinfunction "GND_4") (pintype "power_in"))
      (node (ref "U15") (pin "12") (pinfunction "PGND_12") (pintype "power_in"))
      (node (ref "U15") (pin "15") (pinfunction "EP_15") (pintype "power_in"))
      (node (ref "U15") (pin "21") (pinfunction "EP_21") (pintype "power_in"))
      (node (ref "U15") (pin "6") (pinfunction "AGND_6") (pintype "power_in"))
      (node (ref "U16") (pin "4") (pinfunction "GND_4") (pintype "power_in"))
      (node (ref "U23") (pin "2") (pinfunction "GND_2") (pintype "passive"))
    )
    (net (code "67") (name "TPS65261_V7V") (class "Default")
      (node (ref "C78") (pin "2") (pinfunction "2_2") (pintype "passive"))
      (node (ref "R52") (pin "1") (pinfunction "1_1") (pintype "passive"))
      (node (ref "R54") (pin "1") (pinfunction "1_1") (pintype "passive"))
      (node (ref "R78") (pin "2") (pinfunction "2_2") (pintype "passive"))
      (node (ref "U13") (pin "5") (pinfunction "V7V_5") (pintype "power_in"))
    )
    (net (code "68") (name "VBUS") (class "Default")
      (node (ref "C212") (pin "1") (pinfunction "1_1") (pintype "passive"))
      (node (ref "R127") (pin "1") (pinfunction "1_1") (pintype "passive"))
      (node (ref "R128") (pin "2") (pinfunction "2_2") (pintype "passive"))
      (node (ref "U23") (pin "5") (pinfunction "IN_5") (pintype "passive"))
    )
    (net (code "69") (name "VIN") (class "Default")
      (node (ref "C110") (pin "2") (pinfunction "2_2") (pintype "passive"))
      (node (ref "C111") (pin "1") (pinfunction "1_1") (pintype "passive"))
      (node (ref "C112") (pin "1") (pinfunction "1_1") (pintype "passive"))
      (node (ref "C113") (pin "1") (pinfunction "1_1") (pintype "passive"))
      (node (ref "C114") (pin "1") (pinfunction "1_1") (pintype "passive"))
      (node (ref "C115") (pin "2") (pinfunction "2_2") (pintype "passive"))
      (node (ref "C194") (pin "1") (pinfunction "1_1") (pintype "passive"))
      (node (ref "P5") (pin "1") (pinfunction "VCC_1") (pintype "passive"))
      (node (ref "Q3") (pin "5-6-7-8") (pinfunction "D_5-6-7-8") (pintype "passive"))
      (node (ref "R84") (pin "2") (pinfunction "2_2") (pintype "passive"))
      (node (ref "U15") (pin "20") (pinfunction "VIN_20") (pintype "power_in"))
    )
    (net (code "70") (name "unconnected-(U15-NC-Pad9)") (class "Default")
      (node (ref "U15") (pin "9") (pinfunction "NC_9") (pintype "passive+no_connect"))
    )
    (net (code "71") (name "unconnected-(U15-NC-Pad16)") (class "Default")
      (node (ref "U15") (pin "16") (pinfunction "NC_16") (pintype "passive+no_connect"))
    )
    (net (code "72") (name "unconnected-(U15-SYNCIN-Pad8)") (class "Default")
      (node (ref "U15") (pin "8") (pinfunction "SYNCIN_8") (pintype "input+no_connect"))
    )
    (net (code "73") (name "unconnected-(U15-SYNCOUT-Pad7)") (class "Default")
      (node (ref "U15") (pin "7") (pinfunction "SYNCOUT_7") (pintype "output+no_connect"))
    )
  )
)
